# 5_Accelerometer.net
KiCad netlist of a schematic drawn in Altium Designer
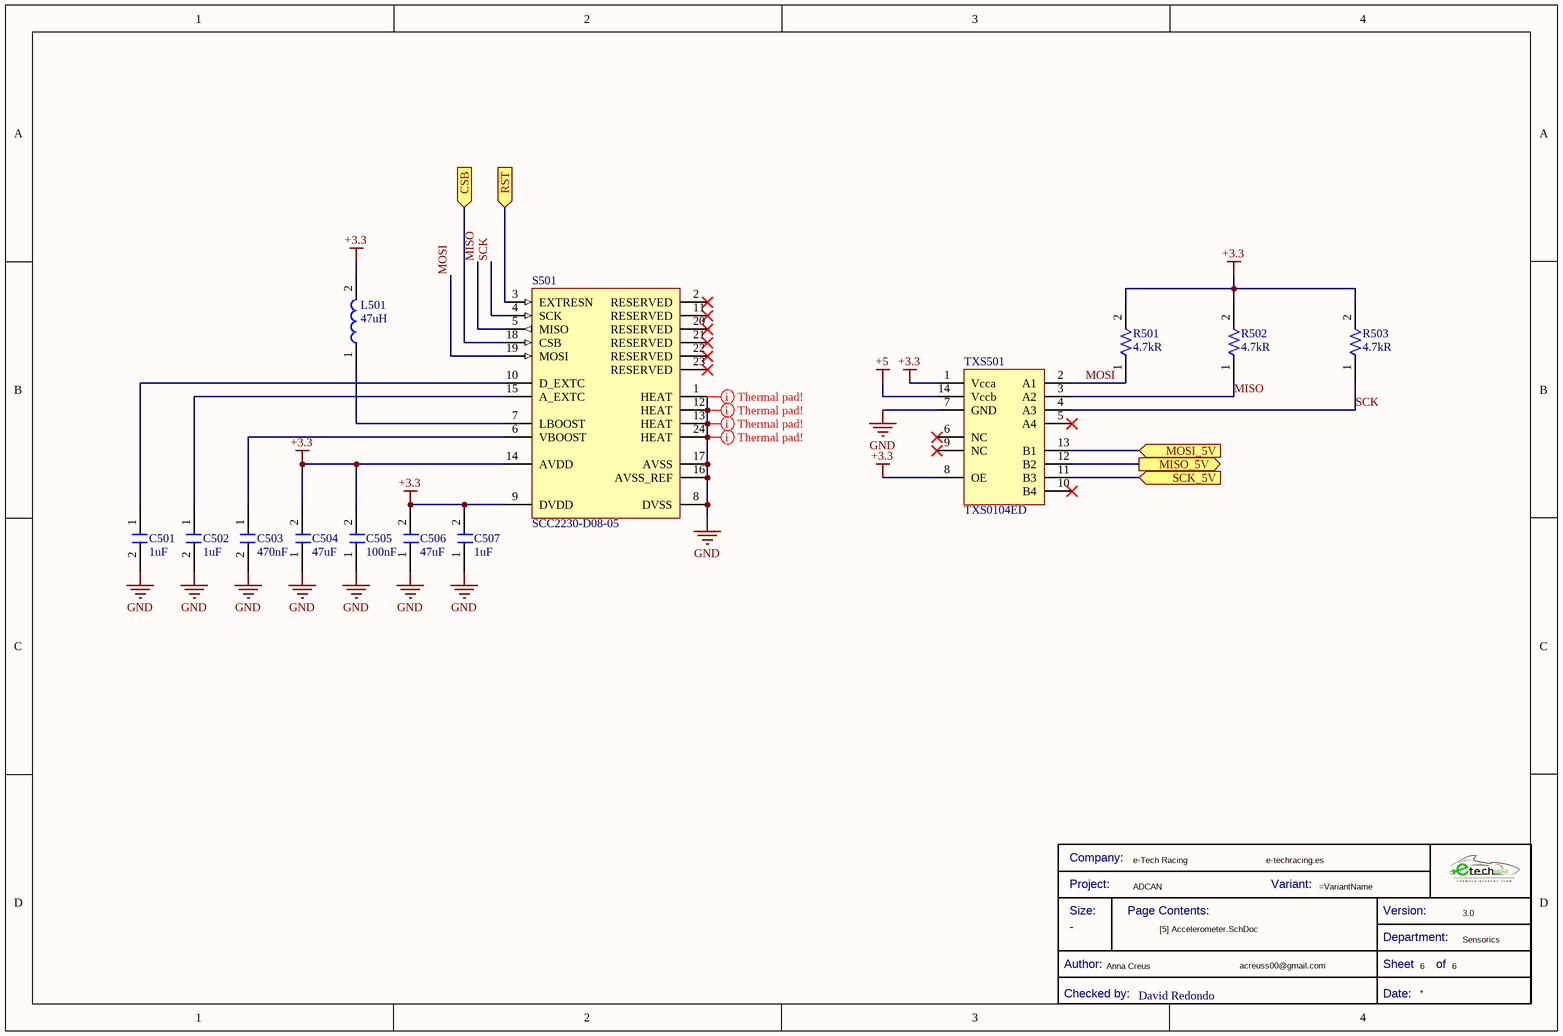
[diagram p0: [5] Accelerometer.SchDoc]

(export (version "E")
  (design (tool "Eeschema 10.0.6"))
  (components
    (comp (ref "C501")
      (value "885012208036")
      (footprint "C1206FNPC-RW")
      (description "Cap Cer 1UF 16V X7R 1206")
      (fields
        (field (name "MANUFACTURER") "Wurth Electronics")
        (field (name "TOLERANCE") "10%")
        (field (name "CAPACITANCE") "1uF")
      )
      (libsource (lib "Passives") (part "C1u-16V-1206FNPC-X7R"))
    )
    (comp (ref "C502")
      (value "885012208036")
      (footprint "C1206FNPC-RW")
      (description "Cap Cer 1UF 16V X7R 1206")
      (fields
        (field (name "MANUFACTURER") "Wurth Electronics")
        (field (name "TOLERANCE") "10%")
        (field (name "CAPACITANCE") "1uF")
      )
      (libsource (lib "Passives") (part "C1u-16V-1206FNPC-X7R"))
    )
    (comp (ref "C503")
      (value "885012208011")
      (footprint "C1206FNPC-RW")
      (description "Cap, 0.47ΜF, 10V, 10%, X7R, 1206")
      (fields (field (name "TOLERANCE") "10%") (field (name "CAPACITANCE") "470nF"))
      (libsource (lib "Passives") (part "C470n-10V-1206FNPC-X7R"))
    )
    (comp (ref "C504")
      (value "885012108012")
      (footprint "C1206FNPC-RW")
      (description "Multilayer Ceramic Capacitor, Wcap-Csgp Series, 47 F, 20%, X5r, 10 V, 1206 [3216 Metric]")
      (fields (field (name "TOLERANCE") "20%") (field (name "CAPACITANCE") "47uF"))
      (libsource (lib "Passives") (part "C47u-10V-1206FNPC-X5R"))
    )
    (comp (ref "C505")
      (value "885012208009")
      (footprint "C1206FNPC-RW")
      (description "Cap, 0.1ΜF, 10V, 10%, X7R, 1206")
      (fields (field (name "TOLERANCE") "10%") (field (name "CAPACITANCE") "100nF"))
      (libsource (lib "Passives") (part "C100n-10V-1206FNPC-X7R"))
    )
    (comp (ref "C506")
      (value "885012108012")
      (footprint "C1206FNPC-RW")
      (description "Multilayer Ceramic Capacitor, Wcap-Csgp Series, 47 F, 20%, X5r, 10 V, 1206 [3216 Metric]")
      (fields (field (name "TOLERANCE") "20%") (field (name "CAPACITANCE") "47uF"))
      (libsource (lib "Passives") (part "C47u-10V-1206FNPC-X5R"))
    )
    (comp (ref "C507")
      (value "885012208036")
      (footprint "C1206FNPC-RW")
      (description "Cap Cer 1UF 16V X7R 1206")
      (fields
        (field (name "MANUFACTURER") "Wurth Electronics")
        (field (name "TOLERANCE") "10%")
        (field (name "CAPACITANCE") "1uF")
      )
      (libsource (lib "Passives") (part "C1u-16V-1206FNPC-X7R"))
    )
    (comp (ref "L501")
      (value "744764147")
      (footprint "L47u-60mA_CF")
      (description "WE-GF Series; Wire-wound SMD Inductor with Ferrite Core; 47 µH")
      (fields (field (name "TOLERANCE") "10%") (field (name "INDUCTANCE") "47uH"))
      (libsource (lib "Passives") (part "L47u-60mA_CF"))
    )
    (comp (ref "R501")
      (value "CRS1206-FX-4701ELF")
      (footprint "R1206FTK-W")
      (description "Res Thick Film 1206 4.7K Ohm 1% 1/2W ±100ppm/°C Molded SMD T/R")
      (fields (field (name "TOLERANCE") "1%") (field (name "RESISTANCE") "4.7kR"))
      (libsource (lib "Passives") (part "R4.7K-1206FTK"))
    )
    (comp (ref "R502")
      (value "CRS1206-FX-4701ELF")
      (footprint "R1206FTK-W")
      (description "Res Thick Film 1206 4.7K Ohm 1% 1/2W ±100ppm/°C Molded SMD T/R")
      (fields (field (name "TOLERANCE") "1%") (field (name "RESISTANCE") "4.7kR"))
      (libsource (lib "Passives") (part "R4.7K-1206FTK"))
    )
    (comp (ref "R503")
      (value "CRS1206-FX-4701ELF")
      (footprint "R1206FTK-W")
      (description "Res Thick Film 1206 4.7K Ohm 1% 1/2W ±100ppm/°C Molded SMD T/R")
      (fields (field (name "TOLERANCE") "1%") (field (name "RESISTANCE") "4.7kR"))
      (libsource (lib "Passives") (part "R4.7K-1206FTK"))
    )
    (comp (ref "S501")
      (value "SCC2230-D08")
      (footprint "Accel_SCC2230-D08")
      (description "Accelerometer and Gyroscope Digital Output 3.3V 24-Pin SOIC T/R")
      (fields (field (name "MANUFACTURER PART NUMBER 1") "SCC2230-D08-05"))
      (libsource (lib "Sensors") (part "Accel_SCC2230-D08"))
    )
    (comp (ref "TXS501")
      (value "TXS0104E")
      (footprint "4bitBVL_TXS0104E")
      (fields (field (name "MANUFACTURER PART NUMBER 1") "TXS0104ED"))
      (libsource (lib "Integrated circuits") (part "4bitBVL_TXS0104E"))
    )
  )
  (nets
    (net (code "1") (name "+3.3") (class "Default")
      (node (ref "C504") (pin "2") (pinfunction "2_2") (pintype "passive"))
      (node (ref "C505") (pin "2") (pinfunction "2_2") (pintype "passive"))
      (node (ref "C506") (pin "2") (pinfunction "2_2") (pintype "passive"))
      (node (ref "C507") (pin "2") (pinfunction "2_2") (pintype "passive"))
      (node (ref "L501") (pin "2") (pinfunction "2_2") (pintype "passive"))
      (node (ref "R501") (pin "2") (pinfunction "2_2") (pintype "passive"))
      (node (ref "R502") (pin "2") (pinfunction "2_2") (pintype "passive"))
      (node (ref "R503") (pin "2") (pinfunction "2_2") (pintype "passive"))
      (node (ref "S501") (pin "14") (pinfunction "AVDD_14") (pintype "passive"))
      (node (ref "S501") (pin "9") (pinfunction "DVDD_9") (pintype "passive"))
      (node (ref "TXS501") (pin "1") (pinfunction "Vcca_1") (pintype "passive"))
      (node (ref "TXS501") (pin "8") (pinfunction "OE_8") (pintype "passive"))
    )
    (net (code "2") (name "+5") (class "Default")
      (node (ref "TXS501") (pin "14") (pinfunction "Vccb_14") (pintype "passive"))
    )
    (net (code "3") (name "/CSB") (class "Default")
      (node (ref "S501") (pin "18") (pinfunction "CSB_18") (pintype "input"))
    )
    (net (code "4") (name "/MISO") (class "Default")
      (node (ref "R502") (pin "1") (pinfunction "1_1") (pintype "passive"))
      (node (ref "S501") (pin "5") (pinfunction "MISO_5") (pintype "output"))
      (node (ref "TXS501") (pin "3") (pinfunction "A2_3") (pintype "passive"))
    )
    (net (code "5") (name "/MISO_5V") (class "Default")
      (node (ref "TXS501") (pin "12") (pinfunction "B2_12") (pintype "passive"))
    )
    (net (code "6") (name "/MOSI") (class "Default")
      (node (ref "R501") (pin "1") (pinfunction "1_1") (pintype "passive"))
      (node (ref "S501") (pin "19") (pinfunction "MOSI_19") (pintype "input"))
      (node (ref "TXS501") (pin "2") (pinfunction "A1_2") (pintype "passive"))
    )
    (net (code "7") (name "/MOSI_5V") (class "Default")
      (node (ref "TXS501") (pin "13") (pinfunction "B1_13") (pintype "passive"))
    )
    (net (code "8") (name "/RST") (class "Default")
      (node (ref "S501") (pin "3") (pinfunction "EXTRESN_3") (pintype "input"))
    )
    (net (code "9") (name "/SCK") (class "Default")
      (node (ref "R503") (pin "1") (pinfunction "1_1") (pintype "passive"))
      (node (ref "S501") (pin "4") (pinfunction "SCK_4") (pintype "input"))
      (node (ref "TXS501") (pin "4") (pinfunction "A3_4") (pintype "passive"))
    )
    (net (code "10") (name "/SCK_5V") (class "Default")
      (node (ref "TXS501") (pin "11") (pinfunction "B3_11") (pintype "passive"))
    )
    (net (code "11") (name "GND") (class "Default")
      (node (ref "C501") (pin "2") (pinfunction "2_2") (pintype "passive"))
      (node (ref "C502") (pin "2") (pinfunction "2_2") (pintype "passive"))
      (node (ref "C503") (pin "2") (pinfunction "2_2") (pintype "passive"))
      (node (ref "C504") (pin "1") (pinfunction "1_1") (pintype "passive"))
      (node (ref "C505") (pin "1") (pinfunction "1_1") (pintype "passive"))
      (node (ref "C506") (pin "1") (pinfunction "1_1") (pintype "passive"))
      (node (ref "C507") (pin "1") (pinfunction "1_1") (pintype "passive"))
      (node (ref "S501") (pin "1") (pinfunction "HEAT_1") (pintype "passive"))
      (node (ref "S501") (pin "12") (pinfunction "HEAT_12") (pintype "passive"))
      (node (ref "S501") (pin "13") (pinfunction "HEAT_13") (pintype "passive"))
      (node (ref "S501") (pin "16") (pinfunction "AVSS_REF_16") (pintype "passive"))
      (node (ref "S501") (pin "17") (pinfunction "AVSS_17") (pintype "passive"))
      (node (ref "S501") (pin "24") (pinfunction "HEAT_24") (pintype "passive"))
      (node (ref "S501") (pin "8") (pinfunction "DVSS_8") (pintype "passive"))
      (node (ref "TXS501") (pin "7") (pinfunction "GND_7") (pintype "passive"))
    )
    (net (code "12") (name "Net-(S501-A_EXTC)") (class "Default")
      (node (ref "C502") (pin "1") (pinfunction "1_1") (pintype "passive"))
      (node (ref "S501") (pin "15") (pinfunction "A_EXTC_15") (pintype "passive"))
    )
    (net (code "13") (name "Net-(S501-D_EXTC)") (class "Default")
      (node (ref "C501") (pin "1") (pinfunction "1_1") (pintype "passive"))
      (node (ref "S501") (pin "10") (pinfunction "D_EXTC_10") (pintype "passive"))
    )
    (net (code "14") (name "Net-(S501-LBOOST)") (class "Default")
      (node (ref "L501") (pin "1") (pinfunction "1_1") (pintype "passive"))
      (node (ref "S501") (pin "7") (pinfunction "LBOOST_7") (pintype "passive"))
    )
    (net (code "15") (name "Net-(S501-VBOOST)") (class "Default")
      (node (ref "C503") (pin "1") (pinfunction "1_1") (pintype "passive"))
      (node (ref "S501") (pin "6") (pinfunction "VBOOST_6") (pintype "passive"))
    )
    (net (code "16") (name "unconnected-(S501-RESERVED-Pad2)") (class "Default")
      (node (ref "S501") (pin "2") (pinfunction "RESERVED_2") (pintype "passive+no_connect"))
    )
    (net (code "17") (name "unconnected-(S501-RESERVED-Pad11)") (class "Default")
      (node (ref "S501") (pin "11") (pinfunction "RESERVED_11") (pintype "passive+no_connect"))
    )
    (net (code "18") (name "unconnected-(S501-RESERVED-Pad20)") (class "Default")
      (node (ref "S501") (pin "20") (pinfunction "RESERVED_20") (pintype "passive+no_connect"))
    )
    (net (code "19") (name "unconnected-(S501-RESERVED-Pad21)") (class "Default")
      (node (ref "S501") (pin "21") (pinfunction "RESERVED_21") (pintype "passive+no_connect"))
    )
    (net (code "20") (name "unconnected-(S501-RESERVED-Pad22)") (class "Default")
      (node (ref "S501") (pin "22") (pinfunction "RESERVED_22") (pintype "passive+no_connect"))
    )
    (net (code "21") (name "unconnected-(S501-RESERVED-Pad23)") (class "Default")
      (node (ref "S501") (pin "23") (pinfunction "RESERVED_23") (pintype "passive+no_connect"))
    )
    (net (code "22") (name "unconnected-(TXS501-A4-Pad5)") (class "Default")
      (node (ref "TXS501") (pin "5") (pinfunction "A4_5") (pintype "passive+no_connect"))
    )
    (net (code "23") (name "unconnected-(TXS501-B4-Pad10)") (class "Default")
      (node (ref "TXS501") (pin "10") (pinfunction "B4_10") (pintype "passive+no_connect"))
    )
    (net (code "24") (name "unconnected-(TXS501-NC-Pad6)") (class "Default")
      (node (ref "TXS501") (pin "6") (pinfunction "NC_6") (pintype "passive+no_connect"))
    )
    (net (code "25") (name "unconnected-(TXS501-NC-Pad9)") (class "Default")
      (node (ref "TXS501") (pin "9") (pinfunction "NC_9") (pintype "passive+no_connect"))
    )
  )
)
